# Stm32_Minimum_Board_V1_0.net
KiCad netlist of a schematic drawn in Altium Designer
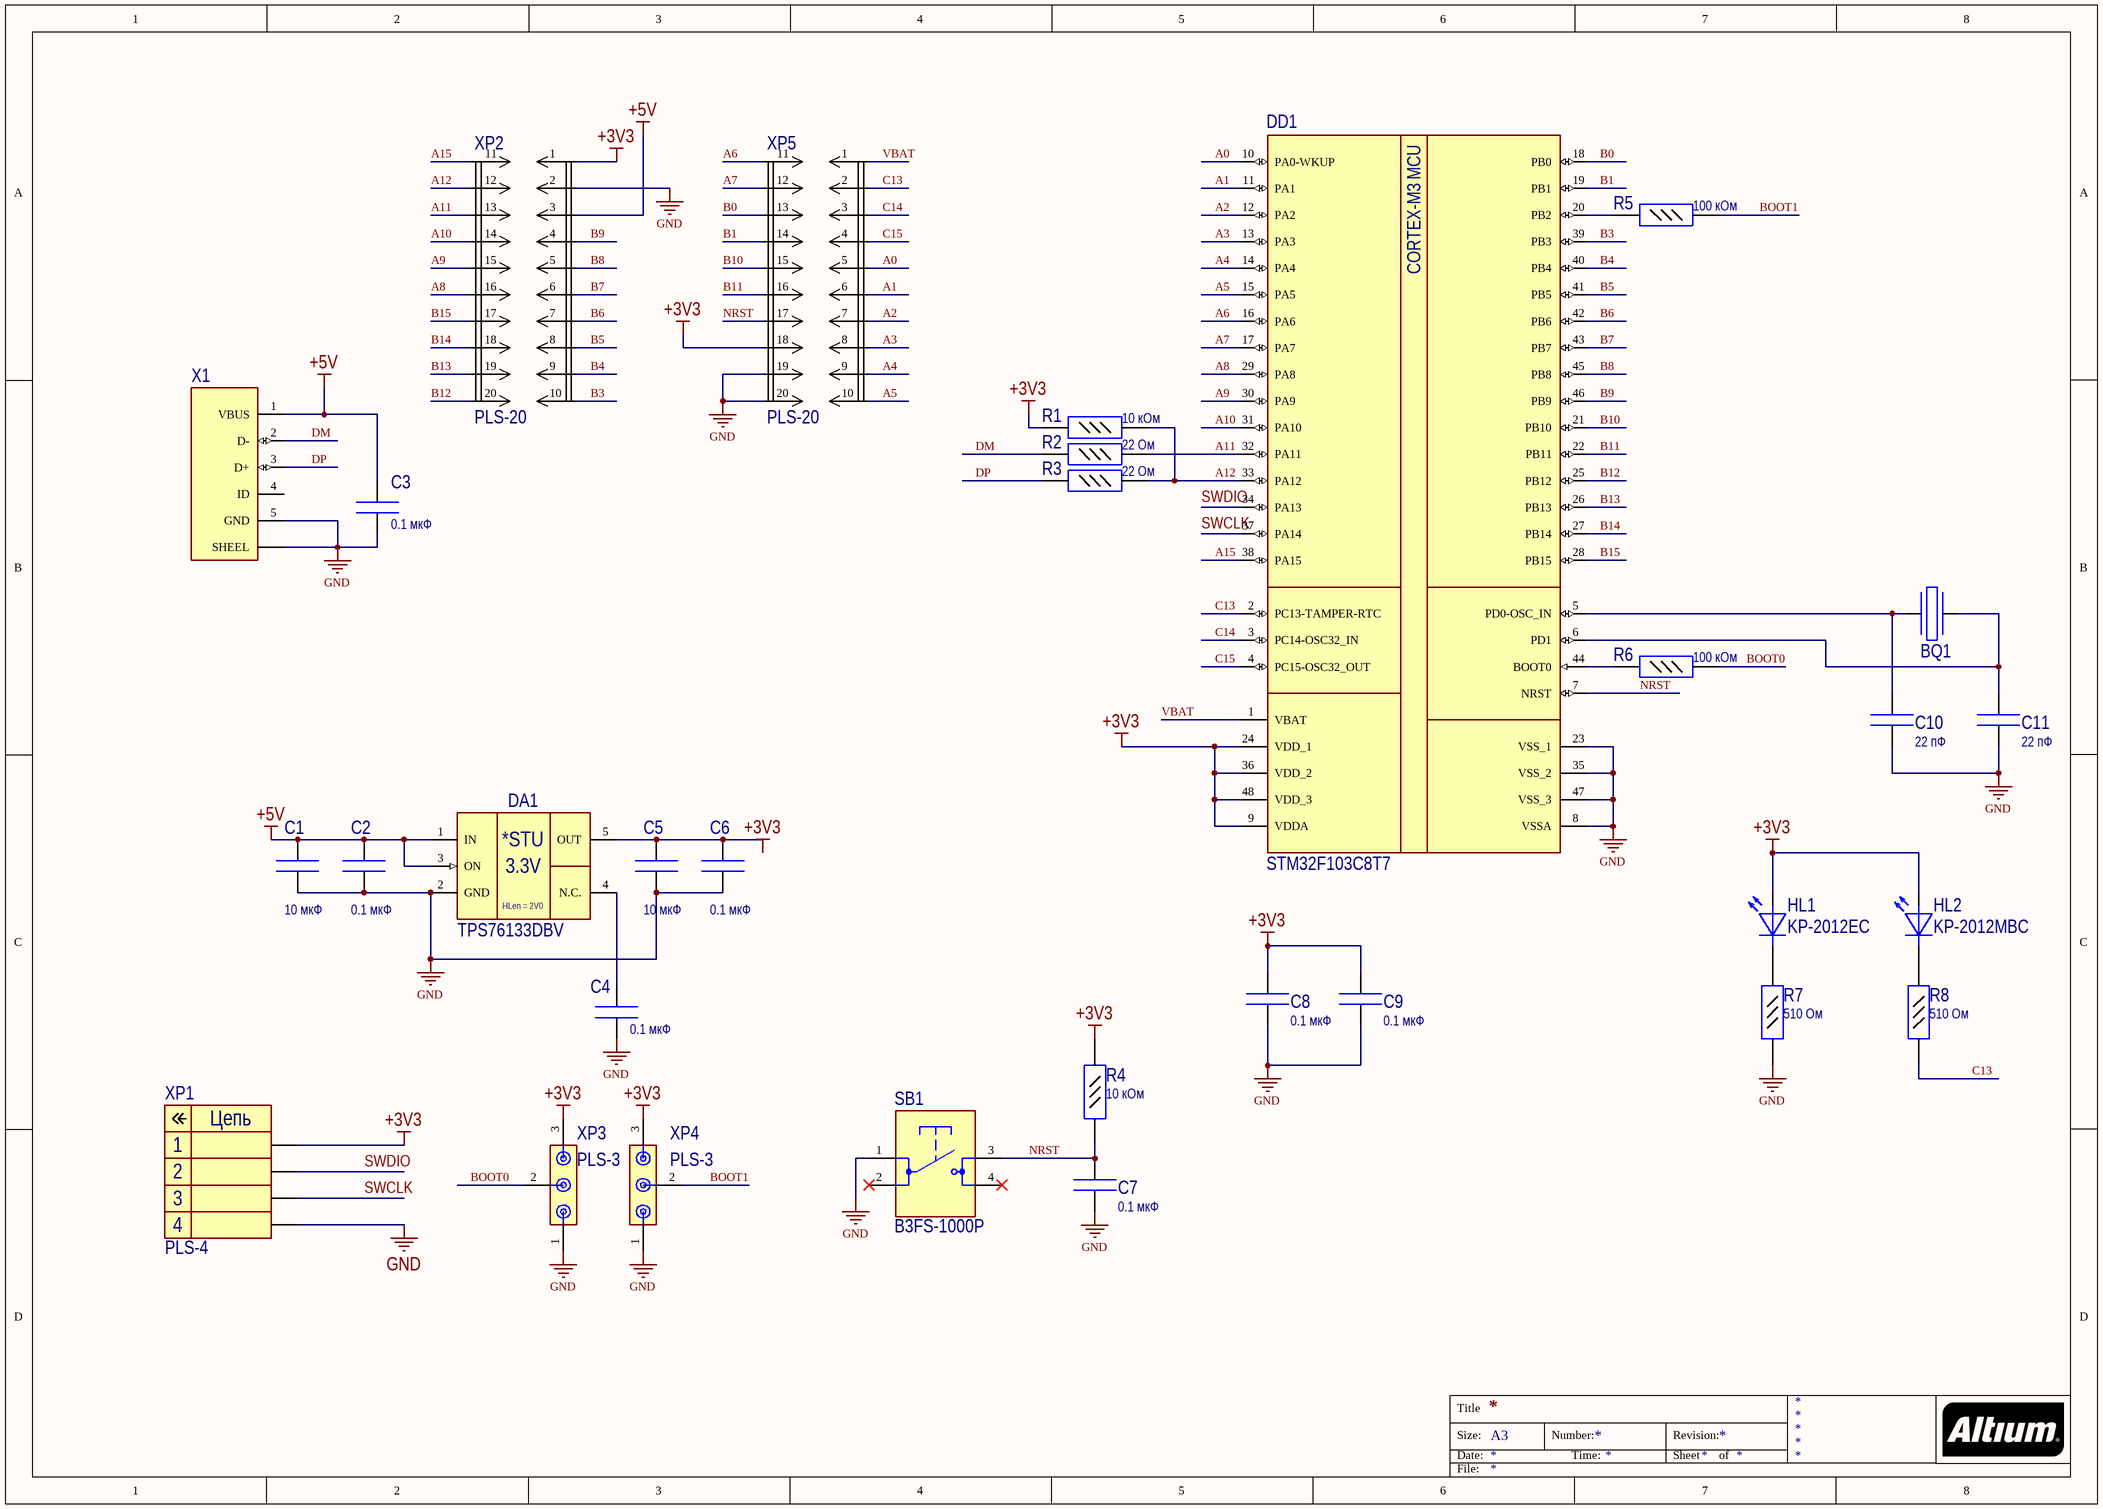
[diagram p0: Stm32_Minimum_Board_V1.0.SchDoc]

(export (version "E")
  (design (tool "Eeschema 10.0.6"))
  (components
    (comp (ref "BQ1")
      (value "HC-49SMD")
      (footprint "HC49-SMD")
      (description "Кварцевый резонатор")
      (libsource (lib "Резонаторы") (part "HC-49SMD"))
    )
    (comp (ref "C1")
      (value "10 мкФ")
      (footprint "CC0805")
      (description "Чип конденсатор керамический")
      (fields (field (name "Comment") "CC0805-X7R-10 мкФ-20%-25В"))
      (libsource (lib "Конденсаторы") (part "CC0805-X7R-#-20%-25В"))
    )
    (comp (ref "C2")
      (value "0.1 мкФ")
      (footprint "CC0603")
      (description "Чип конденсатор керамический")
      (fields (field (name "Comment") "CC0603-X5R-0.1 мкФ-20%-10В"))
      (libsource (lib "Конденсаторы") (part "CC0603-X5R-#-20%-10В"))
    )
    (comp (ref "C3")
      (value "0.1 мкФ")
      (footprint "CC0603")
      (description "Чип конденсатор керамический")
      (fields (field (name "Comment") "CC0603-X5R-0.1 мкФ-20%-10В"))
      (libsource (lib "Конденсаторы") (part "CC0603-X5R-#-20%-10В"))
    )
    (comp (ref "C4")
      (value "0.1 мкФ")
      (footprint "CC0603")
      (description "Чип конденсатор керамический")
      (fields (field (name "Comment") "CC0603-X5R-0.1 мкФ-20%-10В"))
      (libsource (lib "Конденсаторы") (part "CC0603-X5R-#-20%-10В"))
    )
    (comp (ref "C5")
      (value "10 мкФ")
      (footprint "CC0805")
      (description "Чип конденсатор керамический")
      (fields (field (name "Comment") "CC0805-X7R-10 мкФ-20%-25В"))
      (libsource (lib "Конденсаторы") (part "CC0805-X7R-#-20%-25В"))
    )
    (comp (ref "C6")
      (value "0.1 мкФ")
      (footprint "CC0603")
      (description "Чип конденсатор керамический")
      (fields (field (name "Comment") "CC0603-X5R-0.1 мкФ-20%-10В"))
      (libsource (lib "Конденсаторы") (part "CC0603-X5R-#-20%-10В"))
    )
    (comp (ref "C7")
      (value "0.1 мкФ")
      (footprint "CC0603")
      (description "Чип конденсатор керамический")
      (fields (field (name "Comment") "CC0603-X5R-0.1 мкФ-20%-10В"))
      (libsource (lib "Конденсаторы") (part "CC0603-X5R-#-20%-10В"))
    )
    (comp (ref "C8")
      (value "0.1 мкФ")
      (footprint "CC0603")
      (description "Чип конденсатор керамический")
      (fields (field (name "Comment") "CC0603-X5R-0.1 мкФ-20%-10В"))
      (libsource (lib "Конденсаторы") (part "CC0603-X5R-#-20%-10В"))
    )
    (comp (ref "C9")
      (value "0.1 мкФ")
      (footprint "CC0603")
      (description "Чип конденсатор керамический")
      (fields (field (name "Comment") "CC0603-X5R-0.1 мкФ-20%-10В"))
      (libsource (lib "Конденсаторы") (part "CC0603-X5R-#-20%-10В"))
    )
    (comp (ref "C10")
      (value "22 пФ")
      (footprint "CC0603")
      (description "Чип конденсатор керамический")
      (fields (field (name "Comment") "CC0603-X7R-22 пФ-20%-25В"))
      (libsource (lib "Конденсаторы") (part "CC0603-X7R-#-20%-25В"))
    )
    (comp (ref "C11")
      (value "22 пФ")
      (footprint "CC0603")
      (description "Чип конденсатор керамический")
      (fields (field (name "Comment") "CC0603-X7R-22 пФ-20%-25В"))
      (libsource (lib "Конденсаторы") (part "CC0603-X7R-#-20%-25В"))
    )
    (comp (ref "DA1")
      (value "TPS76133DBV")
      (footprint "TSOP-5")
      (description "Стабилизатор 3,3В Vin = 16В, Io =  100 мА, Vdo = 170 мВ")
      (libsource (lib "Микросхемы") (part "TPS76133DBV"))
    )
    (comp (ref "DD1")
      (value "STM32F103C8T7")
      (footprint "LQFP50P700x700-48")
      (description "Микроконтроллер 32bit")
      (libsource (lib "Микросхемы") (part "STM32F103C8T7"))
    )
    (comp (ref "HL1")
      (value "KP-2012EC")
      (footprint "KP-2012-RED")
      (description "Светодиод красный SMD0805")
      (libsource (lib "Индикация") (part "KP-2012EC"))
    )
    (comp (ref "HL2")
      (value "KP-2012MBC")
      (footprint "KP-2012-BL")
      (description "Светодиод голубой SMD0805")
      (libsource (lib "Индикация") (part "KP-2012MBC"))
    )
    (comp (ref "R1")
      (value "10 кОм")
      (footprint "CR0603")
      (description "Чип резистор")
      (fields (field (name "Comment") "CR0603-10 кОм-±5%"))
      (libsource (lib "") (part "CR0603-#-±5%_2"))
    )
    (comp (ref "R2")
      (value "22 Ом")
      (footprint "CR0603")
      (description "Чип резистор")
      (fields (field (name "Comment") "CR0603-22 Ом-±5%"))
      (libsource (lib "") (part "CR0603-#-±5%_1"))
    )
    (comp (ref "R3")
      (value "22 Ом")
      (footprint "CR0603")
      (description "Чип резистор")
      (fields (field (name "Comment") "CR0603-22 Ом-±5%"))
      (libsource (lib "") (part "CR0603-#-±5%_1"))
    )
    (comp (ref "R4")
      (value "10 кОм")
      (footprint "CR0603")
      (description "Чип резистор")
      (fields (field (name "Comment") "CR0603-10 кОм-±5%"))
      (libsource (lib "Резисторы") (part "CR0603-#-±5%"))
    )
    (comp (ref "R5")
      (value "100 кОм")
      (footprint "CR0603")
      (description "Чип резистор")
      (fields (field (name "Comment") "CR0603-100 кОм-±5%"))
      (libsource (lib "") (part "CR0603-#-±5%_1"))
    )
    (comp (ref "R6")
      (value "100 кОм")
      (footprint "CR0603")
      (description "Чип резистор")
      (fields (field (name "Comment") "CR0603-100 кОм-±5%"))
      (libsource (lib "") (part "CR0603-#-±5%_1"))
    )
    (comp (ref "R7")
      (value "510 Ом")
      (footprint "CR0603")
      (description "Чип резистор")
      (fields (field (name "Comment") "CR0603-510 Ом-±5%"))
      (libsource (lib "Резисторы") (part "CR0603-#-±5%"))
    )
    (comp (ref "R8")
      (value "510 Ом")
      (footprint "CR0603")
      (description "Чип резистор")
      (fields (field (name "Comment") "CR0603-510 Ом-±5%"))
      (libsource (lib "Резисторы") (part "CR0603-#-±5%"))
    )
    (comp (ref "SB1")
      (value "B3FS-1000P")
      (footprint "B3FS-10xx")
      (description "Кнопка тактовая 3.1мм")
      (libsource (lib "Переключатели") (part "B3FS-1000P"))
    )
    (comp (ref "X1")
      (value "microUSB-AB (475900001 Molex)")
      (footprint "microUSB-AB PCB (475900001 Molex)")
      (description "microUSB SMD")
      (libsource (lib "Соединители") (part "microUSB-AB (475900001 Molex)"))
    )
    (comp (ref "XP1")
      (value "PLS-4")
      (footprint "PLS-4")
      (description "Штыри на плату однорядные")
      (libsource (lib "Соединители") (part "PLS-4"))
    )
    (comp (ref "XP2")
      (value "PLS-20")
      (footprint "PLS-20")
      (description "Штыри на плату")
      (libsource (lib "Соединители") (part "PLS-20"))
    )
    (comp (ref "XP3")
      (value "PLS-3")
      (footprint "PLS-3")
      (description "Штыри на плату однорядные")
      (libsource (lib "") (part "PLS-3_1"))
    )
    (comp (ref "XP4")
      (value "PLS-3")
      (footprint "PLS-3")
      (description "Штыри на плату однорядные")
      (libsource (lib "Соединители") (part "PLS-3"))
    )
    (comp (ref "XP5")
      (value "PLS-20")
      (footprint "PLS-20")
      (description "Штыри на плату")
      (libsource (lib "Соединители") (part "PLS-20"))
    )
  )
  (nets
    (net (code "1") (name "+3V3") (class "Default")
      (node (ref "C8") (pin "1") (pinfunction "+_1") (pintype "passive"))
      (node (ref "C9") (pin "1") (pinfunction "+_1") (pintype "passive"))
      (node (ref "DD1") (pin "24") (pinfunction "VDD_1_24") (pintype "power_in"))
      (node (ref "DD1") (pin "36") (pinfunction "VDD_2_36") (pintype "power_in"))
      (node (ref "DD1") (pin "48") (pinfunction "VDD_3_48") (pintype "power_in"))
      (node (ref "DD1") (pin "9") (pinfunction "VDDA_9") (pintype "power_in"))
      (node (ref "HL1") (pin "1") (pinfunction "A_1") (pintype "passive"))
      (node (ref "HL2") (pin "1") (pinfunction "A_1") (pintype "passive"))
      (node (ref "R1") (pin "2") (pinfunction "-_2") (pintype "passive"))
      (node (ref "R4") (pin "1") (pinfunction "+_1") (pintype "passive"))
      (node (ref "XP1") (pin "1") (pinfunction "1_1") (pintype "passive"))
      (node (ref "XP2") (pin "1") (pinfunction "1_1") (pintype "passive"))
      (node (ref "XP3") (pin "3") (pinfunction "3_3") (pintype "passive"))
      (node (ref "XP4") (pin "3") (pinfunction "3_3") (pintype "passive"))
      (node (ref "XP5") (pin "18") (pinfunction "18_18") (pintype "passive"))
    )
    (net (code "2") (name "+5V") (class "Default")
      (node (ref "C1") (pin "1") (pinfunction "+_1") (pintype "passive"))
      (node (ref "C2") (pin "1") (pinfunction "+_1") (pintype "passive"))
      (node (ref "C3") (pin "1") (pinfunction "+_1") (pintype "passive"))
      (node (ref "DA1") (pin "1") (pinfunction "IN_1") (pintype "passive"))
      (node (ref "DA1") (pin "3") (pinfunction "ON_3") (pintype "input"))
      (node (ref "X1") (pin "1") (pinfunction "VBUS_1") (pintype "power_in"))
      (node (ref "XP2") (pin "3") (pinfunction "3_3") (pintype "passive"))
    )
    (net (code "3") (name "/A0") (class "Default")
      (node (ref "DD1") (pin "10") (pinfunction "PA0-WKUP_10") (pintype "bidirectional"))
      (node (ref "XP5") (pin "5") (pinfunction "5_5") (pintype "passive"))
    )
    (net (code "4") (name "/A1") (class "Default")
      (node (ref "DD1") (pin "11") (pinfunction "PA1_11") (pintype "bidirectional"))
      (node (ref "XP5") (pin "6") (pinfunction "6_6") (pintype "passive"))
    )
    (net (code "5") (name "/A2") (class "Default")
      (node (ref "DD1") (pin "12") (pinfunction "PA2_12") (pintype "bidirectional"))
      (node (ref "XP5") (pin "7") (pinfunction "7_7") (pintype "passive"))
    )
    (net (code "6") (name "/A3") (class "Default")
      (node (ref "DD1") (pin "13") (pinfunction "PA3_13") (pintype "bidirectional"))
      (node (ref "XP5") (pin "8") (pinfunction "8_8") (pintype "passive"))
    )
    (net (code "7") (name "/A4") (class "Default")
      (node (ref "DD1") (pin "14") (pinfunction "PA4_14") (pintype "bidirectional"))
      (node (ref "XP5") (pin "9") (pinfunction "9_9") (pintype "passive"))
    )
    (net (code "8") (name "/A5") (class "Default")
      (node (ref "DD1") (pin "15") (pinfunction "PA5_15") (pintype "bidirectional"))
      (node (ref "XP5") (pin "10") (pinfunction "10_10") (pintype "passive"))
    )
    (net (code "9") (name "/A6") (class "Default")
      (node (ref "DD1") (pin "16") (pinfunction "PA6_16") (pintype "bidirectional"))
      (node (ref "XP5") (pin "11") (pinfunction "11_11") (pintype "passive"))
    )
    (net (code "10") (name "/A7") (class "Default")
      (node (ref "DD1") (pin "17") (pinfunction "PA7_17") (pintype "bidirectional"))
      (node (ref "XP5") (pin "12") (pinfunction "12_12") (pintype "passive"))
    )
    (net (code "11") (name "/A8") (class "Default")
      (node (ref "DD1") (pin "29") (pinfunction "PA8_29") (pintype "bidirectional"))
      (node (ref "XP2") (pin "16") (pinfunction "16_16") (pintype "passive"))
    )
    (net (code "12") (name "/A9") (class "Default")
      (node (ref "DD1") (pin "30") (pinfunction "PA9_30") (pintype "bidirectional"))
      (node (ref "XP2") (pin "15") (pinfunction "15_15") (pintype "passive"))
    )
    (net (code "13") (name "/A10") (class "Default")
      (node (ref "DD1") (pin "31") (pinfunction "PA10_31") (pintype "bidirectional"))
      (node (ref "XP2") (pin "14") (pinfunction "14_14") (pintype "passive"))
    )
    (net (code "14") (name "/A11") (class "Default")
      (node (ref "DD1") (pin "32") (pinfunction "PA11_32") (pintype "bidirectional"))
      (node (ref "R2") (pin "2") (pinfunction "-_2") (pintype "passive"))
      (node (ref "XP2") (pin "13") (pinfunction "13_13") (pintype "passive"))
    )
    (net (code "15") (name "/A12") (class "Default")
      (node (ref "DD1") (pin "33") (pinfunction "PA12_33") (pintype "bidirectional"))
      (node (ref "R1") (pin "1") (pinfunction "+_1") (pintype "passive"))
      (node (ref "R3") (pin "2") (pinfunction "-_2") (pintype "passive"))
      (node (ref "XP2") (pin "12") (pinfunction "12_12") (pintype "passive"))
    )
    (net (code "16") (name "/A15") (class "Default")
      (node (ref "DD1") (pin "38") (pinfunction "PA15_38") (pintype "bidirectional"))
      (node (ref "XP2") (pin "11") (pinfunction "11_11") (pintype "passive"))
    )
    (net (code "17") (name "/B0") (class "Default")
      (node (ref "DD1") (pin "18") (pinfunction "PB0_18") (pintype "bidirectional"))
      (node (ref "XP5") (pin "13") (pinfunction "13_13") (pintype "passive"))
    )
    (net (code "18") (name "/B1") (class "Default")
      (node (ref "DD1") (pin "19") (pinfunction "PB1_19") (pintype "bidirectional"))
      (node (ref "XP5") (pin "14") (pinfunction "14_14") (pintype "passive"))
    )
    (net (code "19") (name "/B3") (class "Default")
      (node (ref "DD1") (pin "39") (pinfunction "PB3_39") (pintype "bidirectional"))
      (node (ref "XP2") (pin "10") (pinfunction "10_10") (pintype "passive"))
    )
    (net (code "20") (name "/B4") (class "Default")
      (node (ref "DD1") (pin "40") (pinfunction "PB4_40") (pintype "bidirectional"))
      (node (ref "XP2") (pin "9") (pinfunction "9_9") (pintype "passive"))
    )
    (net (code "21") (name "/B5") (class "Default")
      (node (ref "DD1") (pin "41") (pinfunction "PB5_41") (pintype "bidirectional"))
      (node (ref "XP2") (pin "8") (pinfunction "8_8") (pintype "passive"))
    )
    (net (code "22") (name "/B6") (class "Default")
      (node (ref "DD1") (pin "42") (pinfunction "PB6_42") (pintype "bidirectional"))
      (node (ref "XP2") (pin "7") (pinfunction "7_7") (pintype "passive"))
    )
    (net (code "23") (name "/B7") (class "Default")
      (node (ref "DD1") (pin "43") (pinfunction "PB7_43") (pintype "bidirectional"))
      (node (ref "XP2") (pin "6") (pinfunction "6_6") (pintype "passive"))
    )
    (net (code "24") (name "/B8") (class "Default")
      (node (ref "DD1") (pin "45") (pinfunction "PB8_45") (pintype "bidirectional"))
      (node (ref "XP2") (pin "5") (pinfunction "5_5") (pintype "passive"))
    )
    (net (code "25") (name "/B9") (class "Default")
      (node (ref "DD1") (pin "46") (pinfunction "PB9_46") (pintype "bidirectional"))
      (node (ref "XP2") (pin "4") (pinfunction "4_4") (pintype "passive"))
    )
    (net (code "26") (name "/B10") (class "Default")
      (node (ref "DD1") (pin "21") (pinfunction "PB10_21") (pintype "bidirectional"))
      (node (ref "XP5") (pin "15") (pinfunction "15_15") (pintype "passive"))
    )
    (net (code "27") (name "/B11") (class "Default")
      (node (ref "DD1") (pin "22") (pinfunction "PB11_22") (pintype "bidirectional"))
      (node (ref "XP5") (pin "16") (pinfunction "16_16") (pintype "passive"))
    )
    (net (code "28") (name "/B12") (class "Default")
      (node (ref "DD1") (pin "25") (pinfunction "PB12_25") (pintype "bidirectional"))
      (node (ref "XP2") (pin "20") (pinfunction "20_20") (pintype "passive"))
    )
    (net (code "29") (name "/B13") (class "Default")
      (node (ref "DD1") (pin "26") (pinfunction "PB13_26") (pintype "bidirectional"))
      (node (ref "XP2") (pin "19") (pinfunction "19_19") (pintype "passive"))
    )
    (net (code "30") (name "/B14") (class "Default")
      (node (ref "DD1") (pin "27") (pinfunction "PB14_27") (pintype "bidirectional"))
      (node (ref "XP2") (pin "18") (pinfunction "18_18") (pintype "passive"))
    )
    (net (code "31") (name "/B15") (class "Default")
      (node (ref "DD1") (pin "28") (pinfunction "PB15_28") (pintype "bidirectional"))
      (node (ref "XP2") (pin "17") (pinfunction "17_17") (pintype "passive"))
    )
    (net (code "32") (name "/BOOT0") (class "Default")
      (node (ref "R6") (pin "2") (pinfunction "-_2") (pintype "passive"))
      (node (ref "XP3") (pin "2") (pinfunction "2_2") (pintype "passive"))
    )
    (net (code "33") (name "/BOOT1") (class "Default")
      (node (ref "R5") (pin "2") (pinfunction "-_2") (pintype "passive"))
      (node (ref "XP4") (pin "2") (pinfunction "2_2") (pintype "passive"))
    )
    (net (code "34") (name "/C13") (class "Default")
      (node (ref "DD1") (pin "2") (pinfunction "PC13-TAMPER-RTC_2") (pintype "bidirectional"))
      (node (ref "R8") (pin "2") (pinfunction "-_2") (pintype "passive"))
      (node (ref "XP5") (pin "2") (pinfunction "2_2") (pintype "passive"))
    )
    (net (code "35") (name "/C14") (class "Default")
      (node (ref "DD1") (pin "3") (pinfunction "PC14-OSC32_IN_3") (pintype "bidirectional"))
      (node (ref "XP5") (pin "3") (pinfunction "3_3") (pintype "passive"))
    )
    (net (code "36") (name "/C15") (class "Default")
      (node (ref "DD1") (pin "4") (pinfunction "PC15-OSC32_OUT_4") (pintype "bidirectional"))
      (node (ref "XP5") (pin "4") (pinfunction "4_4") (pintype "passive"))
    )
    (net (code "37") (name "/DM") (class "Default")
      (node (ref "R2") (pin "1") (pinfunction "+_1") (pintype "passive"))
      (node (ref "X1") (pin "2") (pinfunction "D-_2") (pintype "bidirectional"))
    )
    (net (code "38") (name "/DP") (class "Default")
      (node (ref "R3") (pin "1") (pinfunction "+_1") (pintype "passive"))
      (node (ref "X1") (pin "3") (pinfunction "D+_3") (pintype "bidirectional"))
    )
    (net (code "39") (name "/NRST") (class "Default")
      (node (ref "C7") (pin "1") (pinfunction "+_1") (pintype "passive"))
      (node (ref "DD1") (pin "7") (pinfunction "NRST_7") (pintype "bidirectional"))
      (node (ref "R4") (pin "2") (pinfunction "-_2") (pintype "passive"))
      (node (ref "SB1") (pin "3") (pintype "passive"))
      (node (ref "XP5") (pin "17") (pinfunction "17_17") (pintype "passive"))
    )
    (net (code "40") (name "/SWCLK") (class "Default")
      (node (ref "DD1") (pin "37") (pinfunction "PA14_37") (pintype "bidirectional"))
      (node (ref "XP1") (pin "3") (pinfunction "3_3") (pintype "passive"))
    )
    (net (code "41") (name "/SWDIO") (class "Default")
      (node (ref "DD1") (pin "34") (pinfunction "PA13_34") (pintype "bidirectional"))
      (node (ref "XP1") (pin "2") (pinfunction "2_2") (pintype "passive"))
    )
    (net (code "42") (name "/VBAT") (class "Default")
      (node (ref "DD1") (pin "1") (pinfunction "VBAT_1") (pintype "power_in"))
      (node (ref "XP5") (pin "1") (pinfunction "1_1") (pintype "passive"))
    )
    (net (code "43") (name "GND") (class "Default")
      (node (ref "C1") (pin "2") (pinfunction "-_2") (pintype "passive"))
      (node (ref "C10") (pin "2") (pinfunction "-_2") (pintype "passive"))
      (node (ref "C11") (pin "2") (pinfunction "-_2") (pintype "passive"))
      (node (ref "C2") (pin "2") (pinfunction "-_2") (pintype "passive"))
      (node (ref "C3") (pin "2") (pinfunction "-_2") (pintype "passive"))
      (node (ref "C4") (pin "2") (pinfunction "-_2") (pintype "passive"))
      (node (ref "C5") (pin "2") (pinfunction "-_2") (pintype "passive"))
      (node (ref "C6") (pin "2") (pinfunction "-_2") (pintype "passive"))
      (node (ref "C7") (pin "2") (pinfunction "-_2") (pintype "passive"))
      (node (ref "C8") (pin "2") (pinfunction "-_2") (pintype "passive"))
      (node (ref "C9") (pin "2") (pinfunction "-_2") (pintype "passive"))
      (node (ref "DA1") (pin "2") (pinfunction "GND_2") (pintype "power_in"))
      (node (ref "DD1") (pin "23") (pinfunction "VSS_1_23") (pintype "power_in"))
      (node (ref "DD1") (pin "35") (pinfunction "VSS_2_35") (pintype "power_in"))
      (node (ref "DD1") (pin "47") (pinfunction "VSS_3_47") (pintype "power_in"))
      (node (ref "DD1") (pin "8") (pinfunction "VSSA_8") (pintype "power_in"))
      (node (ref "R7") (pin "2") (pinfunction "-_2") (pintype "passive"))
      (node (ref "SB1") (pin "1") (pintype "passive"))
      (node (ref "X1") (pin "5") (pinfunction "GND_5") (pintype "power_in"))
      (node (ref "X1") (pin "MH") (pinfunction "SHEEL_MH") (pintype "passive"))
      (node (ref "XP1") (pin "4") (pinfunction "4_4") (pintype "passive"))
      (node (ref "XP2") (pin "2") (pinfunction "2_2") (pintype "passive"))
      (node (ref "XP3") (pin "1") (pinfunction "1_1") (pintype "passive"))
      (node (ref "XP4") (pin "1") (pinfunction "1_1") (pintype "passive"))
      (node (ref "XP5") (pin "19") (pinfunction "19_19") (pintype "passive"))
      (node (ref "XP5") (pin "20") (pinfunction "20_20") (pintype "passive"))
    )
    (net (code "44") (name "Net-(C4-+)") (class "Default")
      (node (ref "C4") (pin "1") (pinfunction "+_1") (pintype "passive"))
      (node (ref "DA1") (pin "4") (pinfunction "N.C._4") (pintype "passive"))
    )
    (net (code "45") (name "Net-(C5-+)") (class "Default")
      (node (ref "C5") (pin "1") (pinfunction "+_1") (pintype "passive"))
      (node (ref "C6") (pin "1") (pinfunction "+_1") (pintype "passive"))
      (node (ref "DA1") (pin "5") (pinfunction "OUT_5") (pintype "power_in"))
    )
    (net (code "46") (name "Net-(C10-+)") (class "Default")
      (node (ref "BQ1") (pin "1") (pintype "passive"))
      (node (ref "C10") (pin "1") (pinfunction "+_1") (pintype "passive"))
      (node (ref "DD1") (pin "5") (pinfunction "PD0-OSC_IN_5") (pintype "bidirectional"))
    )
    (net (code "47") (name "Net-(C11-+)") (class "Default")
      (node (ref "BQ1") (pin "2") (pintype "passive"))
      (node (ref "C11") (pin "1") (pinfunction "+_1") (pintype "passive"))
      (node (ref "DD1") (pin "6") (pinfunction "PD1_6") (pintype "bidirectional"))
    )
    (net (code "48") (name "Net-(DD1-BOOT0)") (class "Default")
      (node (ref "DD1") (pin "44") (pinfunction "BOOT0_44") (pintype "input"))
      (node (ref "R6") (pin "1") (pinfunction "+_1") (pintype "passive"))
    )
    (net (code "49") (name "Net-(DD1-PB2)") (class "Default")
      (node (ref "DD1") (pin "20") (pinfunction "PB2_20") (pintype "bidirectional"))
      (node (ref "R5") (pin "1") (pinfunction "+_1") (pintype "passive"))
    )
    (net (code "50") (name "Net-(HL1-K)") (class "Default")
      (node (ref "HL1") (pin "2") (pinfunction "K_2") (pintype "passive"))
      (node (ref "R7") (pin "1") (pinfunction "+_1") (pintype "passive"))
    )
    (net (code "51") (name "Net-(HL2-K)") (class "Default")
      (node (ref "HL2") (pin "2") (pinfunction "K_2") (pintype "passive"))
      (node (ref "R8") (pin "1") (pinfunction "+_1") (pintype "passive"))
    )
    (net (code "52") (name "unconnected-(SB1-Pad2)") (class "Default")
      (node (ref "SB1") (pin "2") (pintype "passive+no_connect"))
    )
    (net (code "53") (name "unconnected-(SB1-Pad4)") (class "Default")
      (node (ref "SB1") (pin "4") (pintype "passive+no_connect"))
    )
    (net (code "54") (name "unconnected-(X1-ID-Pad4)") (class "Default")
      (node (ref "X1") (pin "4") (pinfunction "ID_4") (pintype "passive"))
    )
  )
)
